# GroundtoFrame.net
KiCad netlist of a schematic drawn in Altium Designer
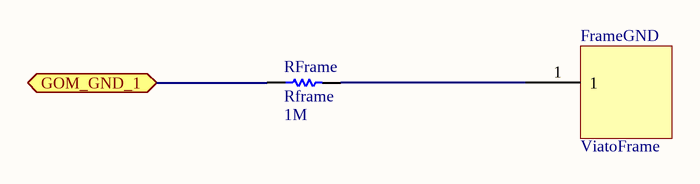
[diagram p0: GroundtoFrame.SchDoc]

(export (version "E")
  (design (tool "Eeschema 10.0.6"))
  (components
    (comp (ref "FrameGND")
      (value "ViatoFrame")
      (footprint "UmbilicalConnectors:ViatoFrame")
      (libsource (lib "UmbilicalBoardV2") (part "ViatoFrame"))
    )
    (comp (ref "RFrame")
      (value "Rframe")
      (footprint "AXIAL-0.3")
      (description "Resistor -  CF14JT1M00CT-ND")
      (fields (field (name "ALTIUM_VALUE") "1M") (field (name "PUBLISHER") "Altium Limited"))
      (libsource (lib "Miscellaneous Devices") (part "Res1"))
    )
  )
  (nets
    (net (code "1") (name "/GOM_GND_1") (class "Default")
      (node (ref "RFrame") (pin "1") (pinfunction "1_1") (pintype "passive"))
    )
    (net (code "2") (name "Net-(FrameGND-Pad1)") (class "Default")
      (node (ref "FrameGND") (pin "1") (pinfunction "1_1") (pintype "passive"))
      (node (ref "RFrame") (pin "2") (pinfunction "2_2") (pintype "passive"))
    )
  )
)
